# sch_Camera.net
KiCad netlist of a schematic drawn in Altium Designer
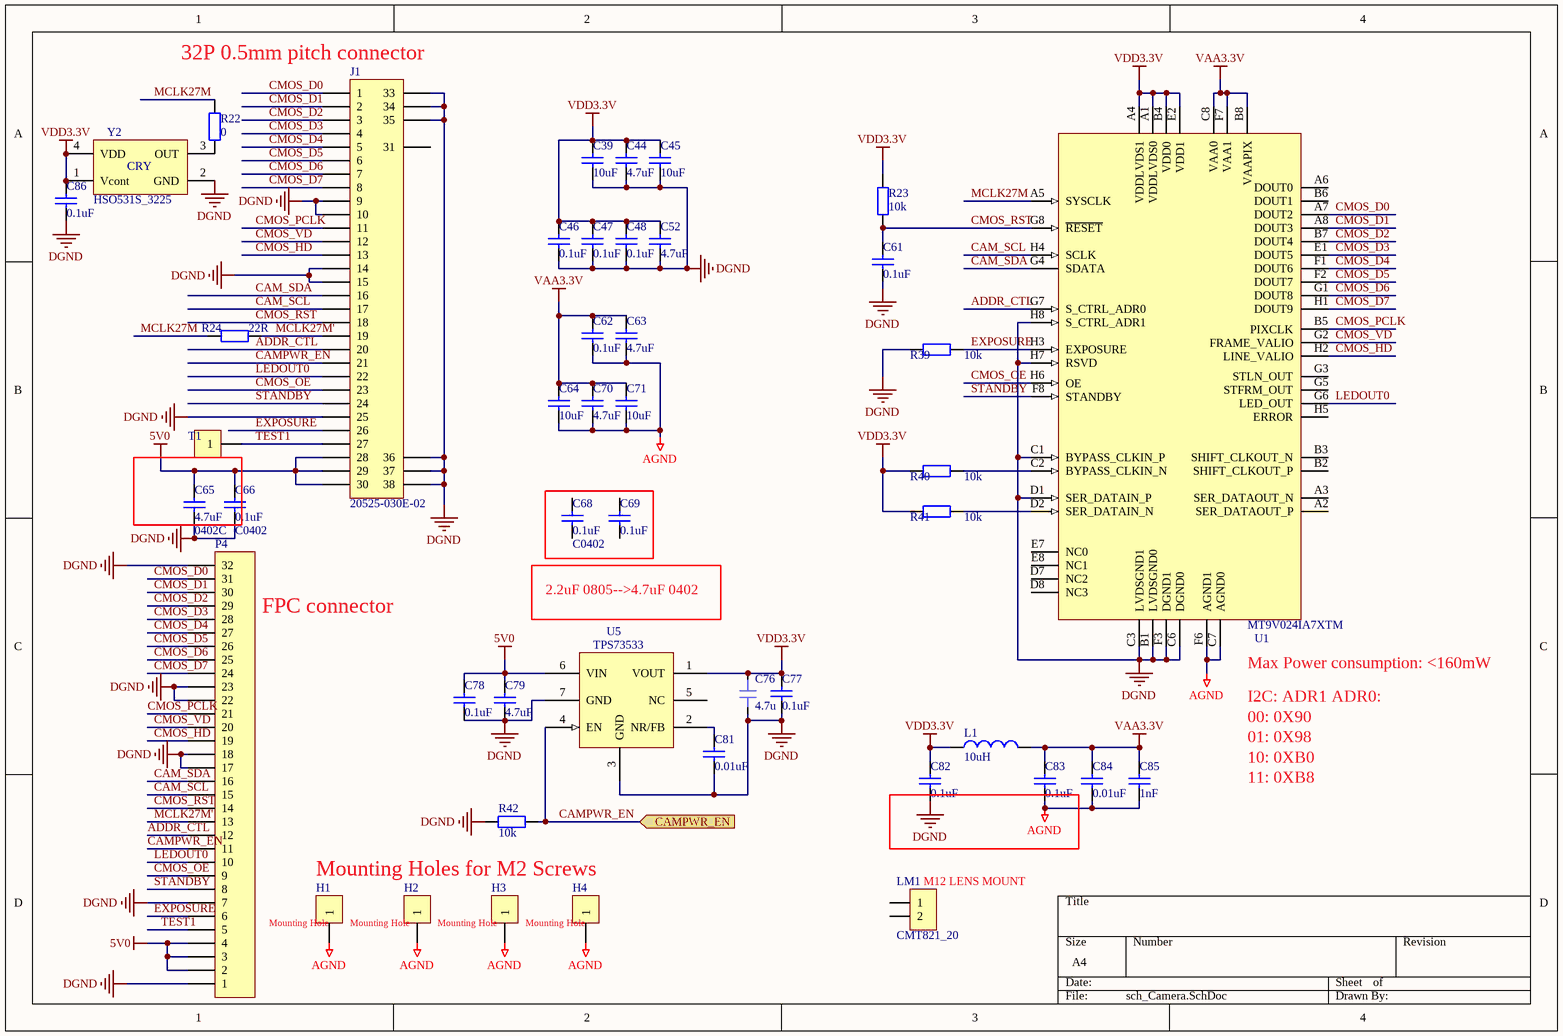
[diagram p0: sch_Camera.SchDoc]

(export (version "E")
  (design (tool "Eeschema 10.0.6"))
  (components
    (comp (ref "C39")
      (value "10uF")
      (footprint "0805C")
      (description "Capacitor")
      (fields (field (name "PUBLISHER") "Altium Limited"))
      (libsource (lib "Miscellaneous Devices") (part "Cap"))
    )
    (comp (ref "C44")
      (value "4.7uF")
      (footprint "0402C")
      (description "Capacitor")
      (fields (field (name "PUBLISHER") "Altium Limited"))
      (libsource (lib "Miscellaneous Devices") (part "Cap"))
    )
    (comp (ref "C45")
      (value "10uF")
      (footprint "0805C")
      (description "Capacitor")
      (fields (field (name "PUBLISHER") "Altium Limited"))
      (libsource (lib "Miscellaneous Devices") (part "Cap"))
    )
    (comp (ref "C46")
      (value "0.1uF")
      (footprint "0402C")
      (description "Capacitor")
      (fields (field (name "PUBLISHER") "Altium Limited"))
      (libsource (lib "Miscellaneous Devices") (part "Cap"))
    )
    (comp (ref "C47")
      (value "0.1uF")
      (footprint "0402C")
      (description "Capacitor")
      (fields (field (name "PUBLISHER") "Altium Limited"))
      (libsource (lib "Miscellaneous Devices") (part "Cap"))
    )
    (comp (ref "C48")
      (value "0.1uF")
      (footprint "0402C")
      (description "Capacitor")
      (fields (field (name "PUBLISHER") "Altium Limited"))
      (libsource (lib "Miscellaneous Devices") (part "Cap"))
    )
    (comp (ref "C52")
      (value "4.7uF")
      (footprint "0402C")
      (description "Capacitor")
      (fields (field (name "PUBLISHER") "Altium Limited"))
      (libsource (lib "Miscellaneous Devices") (part "Cap"))
    )
    (comp (ref "C61")
      (value "0.1uF")
      (footprint "0402C")
      (description "Capacitor")
      (fields (field (name "PUBLISHER") "Altium Limited"))
      (libsource (lib "Miscellaneous Devices") (part "Cap"))
    )
    (comp (ref "C62")
      (value "0.1uF")
      (footprint "0402C")
      (description "Capacitor")
      (fields (field (name "PUBLISHER") "Altium Limited"))
      (libsource (lib "Miscellaneous Devices") (part "Cap"))
    )
    (comp (ref "C63")
      (value "4.7uF")
      (footprint "0402C")
      (description "Capacitor")
      (fields (field (name "PUBLISHER") "Altium Limited"))
      (libsource (lib "Miscellaneous Devices") (part "Cap"))
    )
    (comp (ref "C64")
      (value "10uF")
      (footprint "0805C")
      (description "Capacitor")
      (fields (field (name "PUBLISHER") "Altium Limited"))
      (libsource (lib "Miscellaneous Devices") (part "Cap"))
    )
    (comp (ref "C65")
      (value "4.7uF")
      (footprint "0402C")
      (description "Capacitor")
      (fields (field (name "ALTIUM_VALUE") "0402C") (field (name "PUBLISHER") "Altium Limited"))
      (libsource (lib "Miscellaneous Devices") (part "Cap"))
    )
    (comp (ref "C66")
      (value "0.1uF")
      (footprint "0402C")
      (description "Capacitor")
      (fields (field (name "ALTIUM_VALUE") "C0402") (field (name "PUBLISHER") "Altium Limited"))
      (libsource (lib "Miscellaneous Devices") (part "Cap"))
    )
    (comp (ref "C68")
      (value "0.1uF")
      (footprint "0402C")
      (description "Capacitor")
      (fields (field (name "ALTIUM_VALUE") "C0402") (field (name "PUBLISHER") "Altium Limited"))
      (libsource (lib "Miscellaneous Devices") (part "Cap"))
    )
    (comp (ref "C69")
      (value "0.1uF")
      (footprint "0402C")
      (description "Capacitor")
      (fields (field (name "PUBLISHER") "Altium Limited"))
      (libsource (lib "Miscellaneous Devices") (part "Cap"))
    )
    (comp (ref "C70")
      (value "4.7uF")
      (footprint "0402C")
      (description "Capacitor")
      (fields (field (name "PUBLISHER") "Altium Limited"))
      (libsource (lib "Miscellaneous Devices") (part "Cap"))
    )
    (comp (ref "C71")
      (value "10uF")
      (footprint "0805C")
      (description "Capacitor")
      (fields (field (name "PUBLISHER") "Altium Limited"))
      (libsource (lib "Miscellaneous Devices") (part "Cap"))
    )
    (comp (ref "C76")
      (value "4.7u")
      (footprint "0402C_L")
      (description "CC0402MRX5R5BB475")
      (libsource (lib "V0P1") (part "cap0402"))
    )
    (comp (ref "C77")
      (value "0.1uF")
      (footprint "0402C_L")
      (description "Capacitor")
      (fields (field (name "PUBLISHER") "Altium Limited"))
      (libsource (lib "Miscellaneous Devices") (part "Cap"))
    )
    (comp (ref "C78")
      (value "0.1uF")
      (footprint "0402C")
      (description "Capacitor")
      (fields (field (name "PUBLISHER") "Altium Limited"))
      (libsource (lib "Miscellaneous Devices") (part "Cap"))
    )
    (comp (ref "C79")
      (value "4.7uF")
      (footprint "0402C_L")
      (description "Capacitor")
      (fields (field (name "PUBLISHER") "Altium Limited"))
      (libsource (lib "Miscellaneous Devices") (part "Cap"))
    )
    (comp (ref "C81")
      (value "0.01uF")
      (footprint "0402C_L")
      (description "Capacitor")
      (fields (field (name "PUBLISHER") "Altium Limited"))
      (libsource (lib "Miscellaneous Devices") (part "Cap"))
    )
    (comp (ref "C82")
      (value "0.1uF")
      (footprint "0402C_L")
      (description "Capacitor")
      (fields (field (name "PUBLISHER") "Altium Limited"))
      (libsource (lib "Miscellaneous Devices") (part "Cap"))
    )
    (comp (ref "C83")
      (value "0.1uF")
      (footprint "0402C_L")
      (description "Capacitor")
      (fields (field (name "PUBLISHER") "Altium Limited"))
      (libsource (lib "Miscellaneous Devices") (part "Cap"))
    )
    (comp (ref "C84")
      (value "0.01uF")
      (footprint "0402C_L")
      (description "Capacitor")
      (fields (field (name "PUBLISHER") "Altium Limited"))
      (libsource (lib "Miscellaneous Devices") (part "Cap"))
    )
    (comp (ref "C85")
      (value "1nF")
      (footprint "0402C_L")
      (description "Capacitor")
      (fields (field (name "PUBLISHER") "Altium Limited"))
      (libsource (lib "Miscellaneous Devices") (part "Cap"))
    )
    (comp (ref "C86")
      (value "0.1uF")
      (footprint "0402C")
      (description "Capacitor")
      (fields (field (name "PUBLISHER") "Altium Limited"))
      (libsource (lib "Miscellaneous Devices") (part "Cap"))
    )
    (comp (ref "H1")
      (value "CON1")
      (footprint "PAD_M3_D350_450")
      (description "Connector")
      (libsource (lib "SuperSchLib") (part "CON1"))
    )
    (comp (ref "H2")
      (value "CON1")
      (footprint "PAD_M3_D350_450")
      (description "Connector")
      (libsource (lib "SuperSchLib") (part "CON1"))
    )
    (comp (ref "H3")
      (value "CON1")
      (footprint "PAD_M3_D350_450")
      (description "Connector")
      (libsource (lib "SuperSchLib") (part "CON1"))
    )
    (comp (ref "H4")
      (value "CON1")
      (footprint "PAD_M3_D350_450")
      (description "Connector")
      (libsource (lib "SuperSchLib") (part "CON1"))
    )
    (comp (ref "J1")
      (value "20525-030E-02")
      (footprint "HSA30_P40L196W42H10_20525")
      (libsource (lib "SZG") (part "20525-030E-02"))
    )
    (comp (ref "L1")
      (value "10uH")
      (footprint "0805R")
      (description "Inductor")
      (libsource (lib "SWUST_ROBOT") (part "Inductor"))
    )
    (comp (ref "LM1")
      (value "CMT821_20")
      (footprint "PAD_M3_D350_450")
      (description "Connector")
      (libsource (lib "SuperSchLib") (part "CON2"))
    )
    (comp (ref "P4")
      (value "Header_32")
      (footprint "HS32A_FPC_P50L2350W480H210")
      (description "Header, 30-Pin, Dual row")
      (fields (field (name "PUBLISHER") "Altium Limited"))
      (libsource (lib "TXW") (part "Header 30X2"))
    )
    (comp (ref "R22")
      (value "0")
      (footprint "0402R")
      (description "Resistor")
      (fields (field (name "Comment") "0R") (field (name "PUBLISHER") "Altium Limited"))
      (libsource (lib "") (part "Resistor_3"))
    )
    (comp (ref "R23")
      (value "10k")
      (footprint "0402R")
      (description "Resistor")
      (fields (field (name "Comment") "10K") (field (name "PUBLISHER") "Altium Limited"))
      (libsource (lib "") (part "Resistor_1"))
    )
    (comp (ref "R24")
      (value "22R")
      (footprint "0402R")
      (description "Resistor")
      (fields (field (name "PUBLISHER") "Altium Limited"))
      (libsource (lib "") (part "Resistor_1"))
    )
    (comp (ref "R39")
      (value "10k")
      (footprint "0402R")
      (description "Resistor")
      (fields (field (name "Comment") "10K") (field (name "PUBLISHER") "Altium Limited"))
      (libsource (lib "SZG") (part "Resistor"))
    )
    (comp (ref "R40")
      (value "10k")
      (footprint "0402R")
      (description "Resistor")
      (fields (field (name "Comment") "10K") (field (name "PUBLISHER") "Altium Limited"))
      (libsource (lib "SZG") (part "Resistor"))
    )
    (comp (ref "R41")
      (value "10k")
      (footprint "0402R")
      (description "Resistor")
      (fields (field (name "Comment") "10K") (field (name "PUBLISHER") "Altium Limited"))
      (libsource (lib "SZG") (part "Resistor"))
    )
    (comp (ref "R42")
      (value "10k")
      (footprint "0402R_L")
      (description "Resistor")
      (fields (field (name "Comment") "10K") (field (name "PUBLISHER") "Altium Limited"))
      (libsource (lib "") (part "Resistor_2"))
    )
    (comp (ref "T1")
      (value "CON1")
      (footprint "PAD_TP_D1.2")
      (description "Connector")
      (libsource (lib "") (part "CON1_1"))
    )
    (comp (ref "U1")
      (value "MT9V024IA7XTM")
      (footprint "IBGA52_8X8_P100L90W90H90R")
      (libsource (lib "SZG") (part "MT9V024IA7XTM"))
    )
    (comp (ref "U5")
      (value "TPS73533")
      (footprint "SON6_P65L21W21H8_DRV")
      (libsource (lib "SZG") (part "TPS73533"))
    )
    (comp (ref "Y2")
      (value "HSO531S_3225")
      (footprint "XTAL_3225")
      (description "有源晶振")
      (libsource (lib "超集元件库") (part "CRY"))
    )
  )
  (nets
    (net (code "1") (name "/ADDR_CTL") (class "Default")
      (node (ref "J1") (pin "20") (pinfunction "20_20") (pintype "passive"))
      (node (ref "P4") (pin "12") (pinfunction "12_12") (pintype "passive"))
      (node (ref "U1") (pin "G7") (pinfunction "S_CTRL_ADR0_G7") (pintype "input"))
    )
    (net (code "2") (name "/CAMPWR_EN") (class "Default")
      (node (ref "J1") (pin "21") (pinfunction "21_21") (pintype "passive"))
      (node (ref "P4") (pin "11") (pinfunction "11_11") (pintype "passive"))
      (node (ref "R42") (pin "2") (pinfunction "2_2") (pintype "passive"))
      (node (ref "U5") (pin "4") (pinfunction "EN_4") (pintype "input"))
    )
    (net (code "3") (name "/CAM_SCL") (class "Default")
      (node (ref "J1") (pin "17") (pinfunction "17_17") (pintype "passive"))
      (node (ref "P4") (pin "15") (pinfunction "15_15") (pintype "passive"))
      (node (ref "U1") (pin "H4") (pinfunction "SCLK_H4") (pintype "input"))
    )
    (net (code "4") (name "/CAM_SDA") (class "Default")
      (node (ref "J1") (pin "16") (pinfunction "16_16") (pintype "passive"))
      (node (ref "P4") (pin "16") (pinfunction "16_16") (pintype "passive"))
      (node (ref "U1") (pin "G4") (pinfunction "SDATA_G4") (pintype "passive"))
    )
    (net (code "5") (name "/CMOS_D0") (class "Default")
      (node (ref "J1") (pin "1") (pinfunction "1_1") (pintype "passive"))
      (node (ref "P4") (pin "31") (pinfunction "31_31") (pintype "passive"))
      (node (ref "U1") (pin "A7") (pinfunction "DOUT2_A7") (pintype "passive"))
    )
    (net (code "6") (name "/CMOS_D1") (class "Default")
      (node (ref "J1") (pin "2") (pinfunction "2_2") (pintype "passive"))
      (node (ref "P4") (pin "30") (pinfunction "30_30") (pintype "passive"))
      (node (ref "U1") (pin "A8") (pinfunction "DOUT3_A8") (pintype "passive"))
    )
    (net (code "7") (name "/CMOS_D2") (class "Default")
      (node (ref "J1") (pin "3") (pinfunction "3_3") (pintype "passive"))
      (node (ref "P4") (pin "29") (pinfunction "29_29") (pintype "passive"))
      (node (ref "U1") (pin "B7") (pinfunction "DOUT4_B7") (pintype "passive"))
    )
    (net (code "8") (name "/CMOS_D3") (class "Default")
      (node (ref "J1") (pin "4") (pinfunction "4_4") (pintype "passive"))
      (node (ref "P4") (pin "28") (pinfunction "28_28") (pintype "passive"))
      (node (ref "U1") (pin "E1") (pinfunction "DOUT5_E1") (pintype "passive"))
    )
    (net (code "9") (name "/CMOS_D4") (class "Default")
      (node (ref "J1") (pin "5") (pinfunction "5_5") (pintype "passive"))
      (node (ref "P4") (pin "27") (pinfunction "27_27") (pintype "passive"))
      (node (ref "U1") (pin "F1") (pinfunction "DOUT6_F1") (pintype "passive"))
    )
    (net (code "10") (name "/CMOS_D5") (class "Default")
      (node (ref "J1") (pin "6") (pinfunction "6_6") (pintype "passive"))
      (node (ref "P4") (pin "26") (pinfunction "26_26") (pintype "passive"))
      (node (ref "U1") (pin "F2") (pinfunction "DOUT7_F2") (pintype "passive"))
    )
    (net (code "11") (name "/CMOS_D6") (class "Default")
      (node (ref "J1") (pin "7") (pinfunction "7_7") (pintype "passive"))
      (node (ref "P4") (pin "25") (pinfunction "25_25") (pintype "passive"))
      (node (ref "U1") (pin "G1") (pinfunction "DOUT8_G1") (pintype "passive"))
    )
    (net (code "12") (name "/CMOS_D7") (class "Default")
      (node (ref "J1") (pin "8") (pinfunction "8_8") (pintype "passive"))
      (node (ref "P4") (pin "24") (pinfunction "24_24") (pintype "passive"))
      (node (ref "U1") (pin "H1") (pinfunction "DOUT9_H1") (pintype "passive"))
    )
    (net (code "13") (name "/CMOS_HD") (class "Default")
      (node (ref "J1") (pin "13") (pinfunction "13_13") (pintype "passive"))
      (node (ref "P4") (pin "19") (pinfunction "19_19") (pintype "passive"))
      (node (ref "U1") (pin "H2") (pinfunction "LINE_VALIO_H2") (pintype "passive"))
    )
    (net (code "14") (name "/CMOS_OE") (class "Default")
      (node (ref "J1") (pin "23") (pinfunction "23_23") (pintype "passive"))
      (node (ref "P4") (pin "9") (pinfunction "9_9") (pintype "passive"))
      (node (ref "U1") (pin "H6") (pinfunction "OE_H6") (pintype "input"))
    )
    (net (code "15") (name "/CMOS_PCLK") (class "Default")
      (node (ref "J1") (pin "11") (pinfunction "11_11") (pintype "passive"))
      (node (ref "P4") (pin "21") (pinfunction "21_21") (pintype "passive"))
      (node (ref "U1") (pin "B5") (pinfunction "PIXCLK_B5") (pintype "passive"))
    )
    (net (code "16") (name "/CMOS_RST") (class "Default")
      (node (ref "C61") (pin "2") (pinfunction "2_2") (pintype "passive"))
      (node (ref "J1") (pin "18") (pinfunction "18_18") (pintype "passive"))
      (node (ref "P4") (pin "14") (pinfunction "14_14") (pintype "passive"))
      (node (ref "R23") (pin "1") (pinfunction "1_1") (pintype "passive"))
      (node (ref "U1") (pin "G8") (pinfunction "~{RESET}_G8") (pintype "input"))
    )
    (net (code "17") (name "/CMOS_VD") (class "Default")
      (node (ref "J1") (pin "12") (pinfunction "12_12") (pintype "passive"))
      (node (ref "P4") (pin "20") (pinfunction "20_20") (pintype "passive"))
      (node (ref "U1") (pin "G2") (pinfunction "FRAME_VALIO_G2") (pintype "passive"))
    )
    (net (code "18") (name "/EXPOSURE") (class "Default")
      (node (ref "J1") (pin "26") (pinfunction "26_26") (pintype "passive"))
      (node (ref "P4") (pin "6") (pinfunction "6_6") (pintype "passive"))
      (node (ref "R39") (pin "1") (pinfunction "1_1") (pintype "passive"))
      (node (ref "U1") (pin "H3") (pinfunction "EXPOSURE_H3") (pintype "input"))
    )
    (net (code "19") (name "/LEDOUT0") (class "Default")
      (node (ref "J1") (pin "22") (pinfunction "22_22") (pintype "passive"))
      (node (ref "P4") (pin "10") (pinfunction "10_10") (pintype "passive"))
      (node (ref "U1") (pin "G6") (pinfunction "LED_OUT_G6") (pintype "passive"))
    )
    (net (code "20") (name "/MCLK27M") (class "Default")
      (node (ref "R22") (pin "1") (pinfunction "1_1") (pintype "passive"))
      (node (ref "R24") (pin "1") (pinfunction "1_1") (pintype "passive"))
      (node (ref "U1") (pin "A5") (pinfunction "SYSCLK_A5") (pintype "input"))
    )
    (net (code "21") (name "/MCLK27M'") (class "Default")
      (node (ref "J1") (pin "19") (pinfunction "19_19") (pintype "passive"))
      (node (ref "P4") (pin "13") (pinfunction "13_13") (pintype "passive"))
      (node (ref "R24") (pin "2") (pinfunction "2_2") (pintype "passive"))
    )
    (net (code "22") (name "/STANDBY") (class "Default")
      (node (ref "J1") (pin "24") (pinfunction "24_24") (pintype "passive"))
      (node (ref "P4") (pin "8") (pinfunction "8_8") (pintype "passive"))
      (node (ref "U1") (pin "F8") (pinfunction "STANDBY_F8") (pintype "input"))
    )
    (net (code "23") (name "/TEST1") (class "Default")
      (node (ref "J1") (pin "27") (pinfunction "27_27") (pintype "passive"))
      (node (ref "P4") (pin "5") (pinfunction "5_5") (pintype "passive"))
      (node (ref "T1") (pin "1") (pinfunction "1_1") (pintype "passive"))
    )
    (net (code "24") (name "5V0") (class "Default")
      (node (ref "C65") (pin "2") (pinfunction "2_2") (pintype "passive"))
      (node (ref "C66") (pin "2") (pinfunction "2_2") (pintype "passive"))
      (node (ref "C78") (pin "2") (pinfunction "2_2") (pintype "passive"))
      (node (ref "C79") (pin "2") (pinfunction "2_2") (pintype "passive"))
      (node (ref "J1") (pin "28") (pinfunction "28_28") (pintype "passive"))
      (node (ref "J1") (pin "29") (pinfunction "29_29") (pintype "passive"))
      (node (ref "J1") (pin "30") (pinfunction "30_30") (pintype "passive"))
      (node (ref "P4") (pin "2") (pinfunction "2_2") (pintype "passive"))
      (node (ref "P4") (pin "3") (pinfunction "3_3") (pintype "passive"))
      (node (ref "P4") (pin "4") (pinfunction "4_4") (pintype "passive"))
      (node (ref "U5") (pin "6") (pinfunction "VIN_6") (pintype "passive"))
    )
    (net (code "25") (name "AGND") (class "Default")
      (node (ref "C62") (pin "1") (pinfunction "1_1") (pintype "passive"))
      (node (ref "C63") (pin "1") (pinfunction "1_1") (pintype "passive"))
      (node (ref "C64") (pin "1") (pinfunction "1_1") (pintype "passive"))
      (node (ref "C70") (pin "1") (pinfunction "1_1") (pintype "passive"))
      (node (ref "C71") (pin "1") (pinfunction "1_1") (pintype "passive"))
      (node (ref "C83") (pin "1") (pinfunction "1_1") (pintype "passive"))
      (node (ref "C84") (pin "1") (pinfunction "1_1") (pintype "passive"))
      (node (ref "C85") (pin "1") (pinfunction "1_1") (pintype "passive"))
      (node (ref "H1") (pin "1") (pinfunction "1_1") (pintype "passive"))
      (node (ref "H2") (pin "1") (pinfunction "1_1") (pintype "passive"))
      (node (ref "H3") (pin "1") (pinfunction "1_1") (pintype "passive"))
      (node (ref "H4") (pin "1") (pinfunction "1_1") (pintype "passive"))
      (node (ref "U1") (pin "C7") (pinfunction "AGND0_C7") (pintype "power_in"))
      (node (ref "U1") (pin "F6") (pinfunction "AGND1_F6") (pintype "power_in"))
    )
    (net (code "26") (name "DGND") (class "Default")
      (node (ref "C39") (pin "1") (pinfunction "1_1") (pintype "passive"))
      (node (ref "C44") (pin "1") (pinfunction "1_1") (pintype "passive"))
      (node (ref "C45") (pin "1") (pinfunction "1_1") (pintype "passive"))
      (node (ref "C46") (pin "1") (pinfunction "1_1") (pintype "passive"))
      (node (ref "C47") (pin "1") (pinfunction "1_1") (pintype "passive"))
      (node (ref "C48") (pin "1") (pinfunction "1_1") (pintype "passive"))
      (node (ref "C52") (pin "1") (pinfunction "1_1") (pintype "passive"))
      (node (ref "C61") (pin "1") (pinfunction "1_1") (pintype "passive"))
      (node (ref "C65") (pin "1") (pinfunction "1_1") (pintype "passive"))
      (node (ref "C66") (pin "1") (pinfunction "1_1") (pintype "passive"))
      (node (ref "C76") (pin "2") (pinfunction "2_2") (pintype "passive"))
      (node (ref "C77") (pin "1") (pinfunction "1_1") (pintype "passive"))
      (node (ref "C78") (pin "1") (pinfunction "1_1") (pintype "passive"))
      (node (ref "C79") (pin "1") (pinfunction "1_1") (pintype "passive"))
      (node (ref "C81") (pin "1") (pinfunction "1_1") (pintype "passive"))
      (node (ref "C82") (pin "1") (pinfunction "1_1") (pintype "passive"))
      (node (ref "C86") (pin "1") (pinfunction "1_1") (pintype "passive"))
      (node (ref "J1") (pin "10") (pinfunction "10_10") (pintype "passive"))
      (node (ref "J1") (pin "14") (pinfunction "14_14") (pintype "passive"))
      (node (ref "J1") (pin "15") (pinfunction "15_15") (pintype "passive"))
      (node (ref "J1") (pin "25") (pinfunction "25_25") (pintype "passive"))
      (node (ref "J1") (pin "33") (pinfunction "33_33") (pintype "passive"))
      (node (ref "J1") (pin "34") (pinfunction "34_34") (pintype "passive"))
      (node (ref "J1") (pin "35") (pinfunction "35_35") (pintype "passive"))
      (node (ref "J1") (pin "36") (pinfunction "36_36") (pintype "passive"))
      (node (ref "J1") (pin "37") (pinfunction "37_37") (pintype "passive"))
      (node (ref "J1") (pin "38") (pinfunction "38_38") (pintype "passive"))
      (node (ref "J1") (pin "9") (pinfunction "9_9") (pintype "passive"))
      (node (ref "P4") (pin "1") (pinfunction "1_1") (pintype "passive"))
      (node (ref "P4") (pin "17") (pinfunction "17_17") (pintype "passive"))
      (node (ref "P4") (pin "18") (pinfunction "18_18") (pintype "passive"))
      (node (ref "P4") (pin "22") (pinfunction "22_22") (pintype "passive"))
      (node (ref "P4") (pin "23") (pinfunction "23_23") (pintype "passive"))
      (node (ref "P4") (pin "32") (pinfunction "32_32") (pintype "passive"))
      (node (ref "P4") (pin "7") (pinfunction "7_7") (pintype "passive"))
      (node (ref "R39") (pin "2") (pinfunction "2_2") (pintype "passive"))
      (node (ref "R42") (pin "1") (pinfunction "1_1") (pintype "passive"))
      (node (ref "U1") (pin "B1") (pinfunction "LVDSGND0_B1") (pintype "power_in"))
      (node (ref "U1") (pin "C1") (pinfunction "BYPASS_CLKIN_P_C1") (pintype "input"))
      (node (ref "U1") (pin "C3") (pinfunction "LVDSGND1_C3") (pintype "power_in"))
      (node (ref "U1") (pin "C6") (pinfunction "DGND0_C6") (pintype "power_in"))
      (node (ref "U1") (pin "D1") (pinfunction "SER_DATAIN_P_D1") (pintype "input"))
      (node (ref "U1") (pin "F3") (pinfunction "DGND1_F3") (pintype "power_in"))
      (node (ref "U1") (pin "H7") (pinfunction "RSVD_H7") (pintype "input"))
      (node (ref "U1") (pin "H8") (pinfunction "S_CTRL_ADR1_H8") (pintype "input"))
      (node (ref "U5") (pin "3") (pinfunction "GND_3") (pintype "passive"))
      (node (ref "U5") (pin "7") (pinfunction "GND_7") (pintype "passive"))
      (node (ref "Y2") (pin "2") (pinfunction "GND_2") (pintype "passive"))
    )
    (net (code "27") (name "Net-(U1-BYPASS_CLKIN_N)") (class "Default")
      (node (ref "R40") (pin "1") (pinfunction "1_1") (pintype "passive"))
      (node (ref "U1") (pin "C2") (pinfunction "BYPASS_CLKIN_N_C2") (pintype "input"))
    )
    (net (code "28") (name "Net-(U1-SER_DATAIN_N)") (class "Default")
      (node (ref "R41") (pin "1") (pinfunction "1_1") (pintype "passive"))
      (node (ref "U1") (pin "D2") (pinfunction "SER_DATAIN_N_D2") (pintype "input"))
    )
    (net (code "29") (name "Net-(U5-NR{slash}FB)") (class "Default")
      (node (ref "C81") (pin "2") (pinfunction "2_2") (pintype "passive"))
      (node (ref "U5") (pin "2") (pinfunction "NR/FB_2") (pintype "passive"))
    )
    (net (code "30") (name "Net-(Y2-OUT)") (class "Default")
      (node (ref "R22") (pin "2") (pinfunction "2_2") (pintype "passive"))
      (node (ref "Y2") (pin "3") (pinfunction "OUT_3") (pintype "passive"))
    )
    (net (code "31") (name "VAA3.3V") (class "Default")
      (node (ref "C62") (pin "2") (pinfunction "2_2") (pintype "passive"))
      (node (ref "C63") (pin "2") (pinfunction "2_2") (pintype "passive"))
      (node (ref "C64") (pin "2") (pinfunction "2_2") (pintype "passive"))
      (node (ref "C70") (pin "2") (pinfunction "2_2") (pintype "passive"))
      (node (ref "C71") (pin "2") (pinfunction "2_2") (pintype "passive"))
      (node (ref "C83") (pin "2") (pinfunction "2_2") (pintype "passive"))
      (node (ref "C84") (pin "2") (pinfunction "2_2") (pintype "passive"))
      (node (ref "C85") (pin "2") (pinfunction "2_2") (pintype "passive"))
      (node (ref "L1") (pin "2") (pinfunction "2_2") (pintype "passive"))
      (node (ref "U1") (pin "B8") (pinfunction "VAAPIX_B8") (pintype "power_in"))
      (node (ref "U1") (pin "C8") (pinfunction "VAA0_C8") (pintype "power_in"))
      (node (ref "U1") (pin "F7") (pinfunction "VAA1_F7") (pintype "power_in"))
    )
    (net (code "32") (name "VDD3.3V") (class "Default")
      (node (ref "C39") (pin "2") (pinfunction "2_2") (pintype "passive"))
      (node (ref "C44") (pin "2") (pinfunction "2_2") (pintype "passive"))
      (node (ref "C45") (pin "2") (pinfunction "2_2") (pintype "passive"))
      (node (ref "C46") (pin "2") (pinfunction "2_2") (pintype "passive"))
      (node (ref "C47") (pin "2") (pinfunction "2_2") (pintype "passive"))
      (node (ref "C48") (pin "2") (pinfunction "2_2") (pintype "passive"))
      (node (ref "C52") (pin "2") (pinfunction "2_2") (pintype "passive"))
      (node (ref "C76") (pin "1") (pinfunction "1_1") (pintype "passive"))
      (node (ref "C77") (pin "2") (pinfunction "2_2") (pintype "passive"))
      (node (ref "C82") (pin "2") (pinfunction "2_2") (pintype "passive"))
      (node (ref "C86") (pin "2") (pinfunction "2_2") (pintype "passive"))
      (node (ref "L1") (pin "1") (pinfunction "1_1") (pintype "passive"))
      (node (ref "R23") (pin "2") (pinfunction "2_2") (pintype "passive"))
      (node (ref "R40") (pin "2") (pinfunction "2_2") (pintype "passive"))
      (node (ref "R41") (pin "2") (pinfunction "2_2") (pintype "passive"))
      (node (ref "U1") (pin "A1") (pinfunction "VDDLVDS0_A1") (pintype "power_in"))
      (node (ref "U1") (pin "A4") (pinfunction "VDDLVDS1_A4") (pintype "power_in"))
      (node (ref "U1") (pin "B4") (pinfunction "VDD0_B4") (pintype "power_in"))
      (node (ref "U1") (pin "E2") (pinfunction "VDD1_E2") (pintype "power_in"))
      (node (ref "U5") (pin "1") (pinfunction "VOUT_1") (pintype "passive"))
      (node (ref "Y2") (pin "1") (pinfunction "Vcont_1") (pintype "passive"))
      (node (ref "Y2") (pin "4") (pinfunction "VDD_4") (pintype "passive"))
    )
    (net (code "33") (name "unconnected-(C68-Pad1)") (class "Default")
      (node (ref "C68") (pin "1") (pinfunction "1_1") (pintype "passive"))
    )
    (net (code "34") (name "unconnected-(C68-Pad2)") (class "Default")
      (node (ref "C68") (pin "2") (pinfunction "2_2") (pintype "passive"))
    )
    (net (code "35") (name "unconnected-(C69-Pad1)") (class "Default")
      (node (ref "C69") (pin "1") (pinfunction "1_1") (pintype "passive"))
    )
    (net (code "36") (name "unconnected-(C69-Pad2)") (class "Default")
      (node (ref "C69") (pin "2") (pinfunction "2_2") (pintype "passive"))
    )
    (net (code "37") (name "unconnected-(J1-Pad31)") (class "Default")
      (node (ref "J1") (pin "31") (pinfunction "31_31") (pintype "passive"))
    )
    (net (code "38") (name "unconnected-(LM1-Pad1)") (class "Default")
      (node (ref "LM1") (pin "1") (pinfunction "1_1") (pintype "passive"))
    )
    (net (code "39") (name "unconnected-(LM1-Pad2)") (class "Default")
      (node (ref "LM1") (pin "2") (pinfunction "2_2") (pintype "passive"))
    )
    (net (code "40") (name "unconnected-(U1-DOUT0-PadA6)") (class "Default")
      (node (ref "U1") (pin "A6") (pinfunction "DOUT0_A6") (pintype "passive"))
    )
    (net (code "41") (name "unconnected-(U1-DOUT1-PadB6)") (class "Default")
      (node (ref "U1") (pin "B6") (pinfunction "DOUT1_B6") (pintype "passive"))
    )
    (net (code "42") (name "unconnected-(U1-ERROR-PadH5)") (class "Default")
      (node (ref "U1") (pin "H5") (pinfunction "ERROR_H5") (pintype "passive"))
    )
    (net (code "43") (name "unconnected-(U1-NC0-PadE7)") (class "Default")
      (node (ref "U1") (pin "E7") (pinfunction "NC0_E7") (pintype "passive"))
    )
    (net (code "44") (name "unconnected-(U1-NC1-PadE8)") (class "Default")
      (node (ref "U1") (pin "E8") (pinfunction "NC1_E8") (pintype "power_in"))
    )
    (net (code "45") (name "unconnected-(U1-NC2-PadD7)") (class "Default")
      (node (ref "U1") (pin "D7") (pinfunction "NC2_D7") (pintype "power_in"))
    )
    (net (code "46") (name "unconnected-(U1-NC3-PadD8)") (class "Default")
      (node (ref "U1") (pin "D8") (pinfunction "NC3_D8") (pintype "power_in"))
    )
    (net (code "47") (name "unconnected-(U1-SER_DATAOUT_N-PadA3)") (class "Default")
      (node (ref "U1") (pin "A3") (pinfunction "SER_DATAOUT_N_A3") (pintype "passive"))
    )
    (net (code "48") (name "unconnected-(U1-SER_DATAOUT_P-PadA2)") (class "Default")
      (node (ref "U1") (pin "A2") (pinfunction "SER_DATAOUT_P_A2") (pintype "passive"))
    )
    (net (code "49") (name "unconnected-(U1-SHIFT_CLKOUT_N-PadB3)") (class "Default")
      (node (ref "U1") (pin "B3") (pinfunction "SHIFT_CLKOUT_N_B3") (pintype "passive"))
    )
    (net (code "50") (name "unconnected-(U1-SHIFT_CLKOUT_P-PadB2)") (class "Default")
      (node (ref "U1") (pin "B2") (pinfunction "SHIFT_CLKOUT_P_B2") (pintype "passive"))
    )
    (net (code "51") (name "unconnected-(U1-STFRM_OUT-PadG5)") (class "Default")
      (node (ref "U1") (pin "G5") (pinfunction "STFRM_OUT_G5") (pintype "passive"))
    )
    (net (code "52") (name "unconnected-(U1-STLN_OUT-PadG3)") (class "Default")
      (node (ref "U1") (pin "G3") (pinfunction "STLN_OUT_G3") (pintype "passive"))
    )
    (net (code "53") (name "unconnected-(U5-NC-Pad5)") (class "Default")
      (node (ref "U5") (pin "5") (pinfunction "NC_5") (pintype "passive"))
    )
  )
)
